# PL2303A.net
KiCad netlist of a schematic drawn in Altium Designer
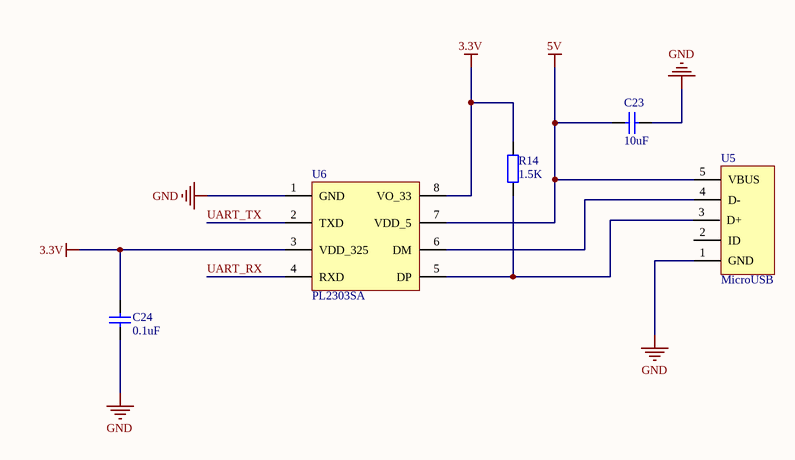
[diagram p0: PL2303A.SchDoc]

(export (version "E")
  (design (tool "Eeschema 10.0.6"))
  (components
    (comp (ref "C23")
      (value "10uF")
      (footprint "0603")
      (description "ceramic")
      (libsource (lib "ToponLib") (part "Cap1"))
    )
    (comp (ref "C24")
      (value "0.1uF")
      (footprint "0603")
      (description "ceramic")
      (libsource (lib "ToponLib") (part "Cap1"))
    )
    (comp (ref "R14") (value "1.5K") (footprint "0603") (libsource (lib "ToponLib") (part "Res")))
    (comp (ref "U5")
      (value "MicroUSB")
      (footprint "Micro-USB")
      (libsource (lib "ToponLib") (part "MicroUSB_B"))
    )
    (comp (ref "U6") (value "PL2303SA") (footprint "SOP-8") (libsource (lib "ToponLib") (part "PL2303SA")))
  )
  (nets
    (net (code "1") (name "/UART_RX") (class "Default")
      (node (ref "U6") (pin "4") (pinfunction "RXD_4") (pintype "passive"))
    )
    (net (code "2") (name "/UART_TX") (class "Default")
      (node (ref "U6") (pin "2") (pinfunction "TXD_2") (pintype "passive"))
    )
    (net (code "3") (name "3.3V") (class "Default")
      (node (ref "C24") (pin "2") (pinfunction "2_2") (pintype "passive"))
      (node (ref "R14") (pin "2") (pinfunction "2_2") (pintype "passive"))
      (node (ref "U6") (pin "3") (pinfunction "VDD_325_3") (pintype "passive"))
      (node (ref "U6") (pin "8") (pinfunction "VO_33_8") (pintype "passive"))
    )
    (net (code "4") (name "5V") (class "Default")
      (node (ref "C23") (pin "2") (pinfunction "2_2") (pintype "passive"))
      (node (ref "U5") (pin "5") (pinfunction "VBUS_5") (pintype "passive"))
      (node (ref "U6") (pin "7") (pinfunction "VDD_5_7") (pintype "passive"))
    )
    (net (code "5") (name "GND") (class "Default")
      (node (ref "C23") (pin "1") (pinfunction "1_1") (pintype "passive"))
      (node (ref "C24") (pin "1") (pinfunction "1_1") (pintype "passive"))
      (node (ref "U5") (pin "1") (pinfunction "GND_1") (pintype "passive"))
      (node (ref "U6") (pin "1") (pinfunction "GND_1") (pintype "passive"))
    )
    (net (code "6") (name "Net-(U5-D+)") (class "Default")
      (node (ref "R14") (pin "1") (pinfunction "1_1") (pintype "passive"))
      (node (ref "U5") (pin "3") (pinfunction "D+_3") (pintype "passive"))
      (node (ref "U6") (pin "5") (pinfunction "DP_5") (pintype "passive"))
    )
    (net (code "7") (name "Net-(U5-D-)") (class "Default")
      (node (ref "U5") (pin "4") (pinfunction "D-_4") (pintype "passive"))
      (node (ref "U6") (pin "6") (pinfunction "DM_6") (pintype "passive"))
    )
    (net (code "8") (name "unconnected-(U5-ID-Pad2)") (class "Default")
      (node (ref "U5") (pin "2") (pinfunction "ID_2") (pintype "passive"))
    )
  )
)
